# Encoder.net
KiCad netlist of a schematic drawn in Altium Designer
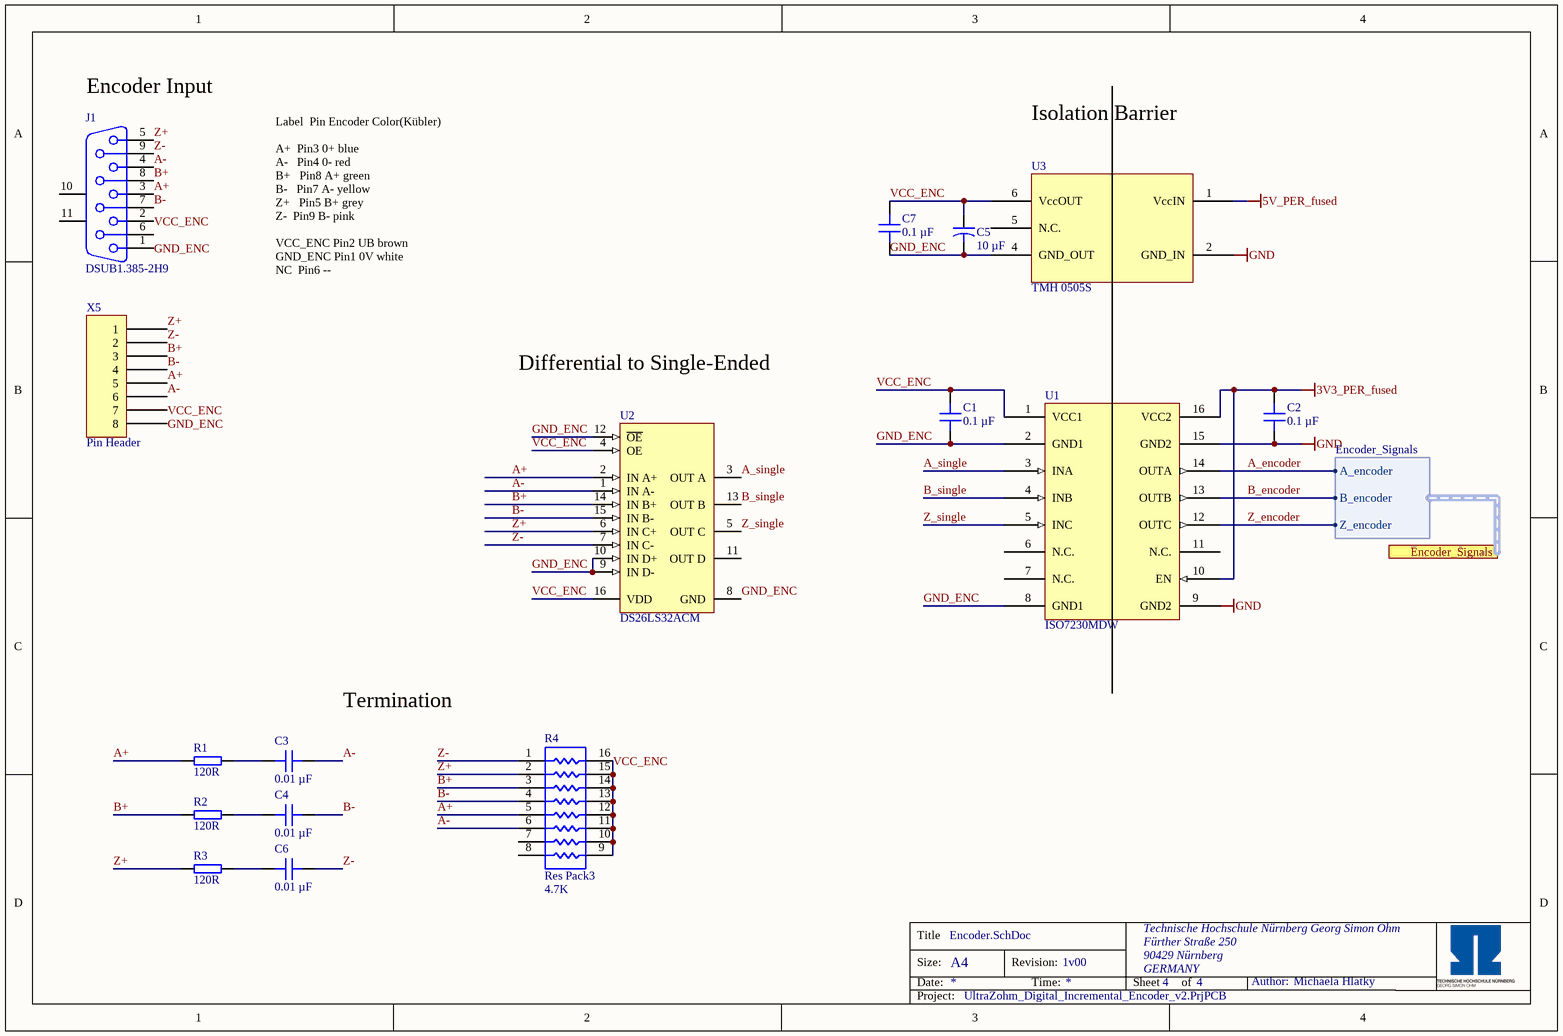
[diagram p0: Encoder.SchDoc]

(export (version "E")
  (design (tool "Eeschema 10.0.6"))
  (components
    (comp (ref "C1")
      (value "0.1 µF")
      (footprint "C_0805")
      (description "Capacitor 0805, 50 VDC, 0.1 µF, X7R")
      (fields
        (field (name "MANUFACTURER PART NUMBER") "C0805C104J5RECTU")
        (field (name "MANUFACTURER") "KEMET")
        (field (name "CREATED FROM") "MGremer")
      )
      (libsource (lib "user") (part "Capacitor"))
    )
    (comp (ref "C2")
      (value "0.1 µF")
      (footprint "C_0805")
      (description "Capacitor 0805, 50 VDC, 0.1 µF, X7R")
      (fields
        (field (name "MANUFACTURER PART NUMBER") "C0805C104J5RECTU")
        (field (name "MANUFACTURER") "KEMET")
        (field (name "CREATED FROM") "MGremer")
      )
      (libsource (lib "user") (part "Capacitor"))
    )
    (comp (ref "C3")
      (value "0.01 µF")
      (footprint "C_0805")
      (description "Capacitor 0805, 100 VDC, 0.01 µF, X7R")
      (fields
        (field (name "MANUFACTURER PART NUMBER") "GRM21BR72A103KA01L")
        (field (name "MANUFACTURER") "Murata Electronics")
        (field (name "CREATED FROM") "MGremer")
      )
      (libsource (lib "user") (part "Capacitor"))
    )
    (comp (ref "C4")
      (value "0.01 µF")
      (footprint "C_0805")
      (description "Capacitor 0805, 100 VDC, 0.01 µF, X7R")
      (fields
        (field (name "MANUFACTURER PART NUMBER") "GRM21BR72A103KA01L")
        (field (name "MANUFACTURER") "Murata Electronics")
        (field (name "CREATED FROM") "MGremer")
      )
      (libsource (lib "user") (part "Capacitor"))
    )
    (comp (ref "C5")
      (value "10 µF")
      (footprint "CAPR5-4X5")
      (description "Capacitor; 2 Leads")
      (fields
        (field (name "MANUFACTURER PART NUMBER") "CAPR5-4X5")
        (field (name "PUBLISHER") "Altium Limited")
        (field (name "CREATED FROM") "MHlatky")
      )
      (libsource (lib "user") (part "Cap2"))
    )
    (comp (ref "C6")
      (value "0.01 µF")
      (footprint "C_0805")
      (description "Capacitor 0805, 100 VDC, 0.01 µF, X7R")
      (fields
        (field (name "MANUFACTURER PART NUMBER") "GRM21BR72A103KA01L")
        (field (name "MANUFACTURER") "Murata Electronics")
        (field (name "CREATED FROM") "MGremer")
      )
      (libsource (lib "user") (part "Capacitor"))
    )
    (comp (ref "C7")
      (value "0.1 µF")
      (footprint "C_0805")
      (description "Capacitor 0805, 50 VDC, 0.1 µF, X7R")
      (fields
        (field (name "MANUFACTURER PART NUMBER") "C0805C104J5RECTU")
        (field (name "MANUFACTURER") "KEMET")
        (field (name "CREATED FROM") "MGremer")
      )
      (libsource (lib "user") (part "Capacitor"))
    )
    (comp (ref "J1")
      (value "DSUB1.385-2H9")
      (footprint "DSUB1.385-2H9")
      (description "Connector; D Subminiature; 9 Position; Right Angle; Pitch 1.385 mm")
      (fields
        (field (name "MANUFACTURER") "Altium")
        (field (name "PUBLISHER") "Altium Limited")
        (field (name "CREATED FROM") "MHlatky")
      )
      (libsource (lib "user") (part "D Connector 9"))
    )
    (comp (ref "R1")
      (value "120R")
      (footprint "RES 0603_1608")
      (description "SMD resistor E24 series")
      (fields
        (field (name "MANUFACTURER PART NUMBER") "RK73B1JTTD121J")
        (field (name "MANUFACTURER") "KOA Speer")
        (field (name "CREATED FROM") "MGremer")
      )
      (libsource (lib "user") (part "Resistor"))
    )
    (comp (ref "R2")
      (value "120R")
      (footprint "RES 0603_1608")
      (description "SMD resistor E24 series")
      (fields
        (field (name "MANUFACTURER PART NUMBER") "RK73B1JTTD121J")
        (field (name "MANUFACTURER") "KOA Speer")
        (field (name "CREATED FROM") "MGremer")
      )
      (libsource (lib "user") (part "Resistor"))
    )
    (comp (ref "R3")
      (value "120R")
      (footprint "RES 0603_1608")
      (description "SMD resistor E24 series")
      (fields
        (field (name "MANUFACTURER PART NUMBER") "RK73B1JTTD121J")
        (field (name "MANUFACTURER") "KOA Speer")
        (field (name "CREATED FROM") "MGremer")
      )
      (libsource (lib "user") (part "Resistor"))
    )
    (comp (ref "R4")
      (value "Res Pack3")
      (footprint "SO-16_N")
      (description "SOIC, 16-Leads, Body 9.9x3.9mm, Pitch 1.27mm, IPC Medium Density")
      (fields
        (field (name "ALTIUM_VALUE") "4.7K")
        (field (name "PUBLISHER") "Altium Limited")
        (field (name "CREATED FROM") "MHlatky")
      )
      (libsource (lib "user") (part "Res Pack3"))
    )
    (comp (ref "U1")
      (value "ISO7230MDW")
      (footprint "TI ISO7230 SOIC")
      (description "ISO723xx High-Speed, Triple-Channel Digital Isolators")
      (fields (field (name "MANUFACTURER") "Analog Devices") (field (name "CREATED FROM") "MHlatky"))
      (libsource (lib "user") (part "TI ISO7230"))
    )
    (comp (ref "U2")
      (value "DS26LS32ACM")
      (footprint "M16A_M")
      (description "DS26LS32AC/DS26LS32C/DS26LS32M/DS26LS33M Quad Differential Line Receivers")
      (fields
        (field (name "MANUFACTURER") "Texas Instruments")
        (field (name "PUBLISHER") "Altium Limited")
        (field (name "CREATED FROM") "MHlatky")
      )
      (libsource (lib "user") (part "DS26LS32ACM"))
    )
    (comp (ref "U3")
      (value "TMH 0505S")
      (footprint "SIL-6(7)")
      (fields (field (name "MANUFACTURER") "Traco") (field (name "CREATED FROM") "MHlatky"))
      (libsource (lib "user") (part "TRACO TMH 0505S"))
    )
    (comp (ref "X5")
      (value "Pin Header")
      (footprint "HDR1X8")
      (description "8 Pin")
      (fields (field (name "MANUFACTURER PART NUMBER") "HDR1X8") (field (name "CREATED FROM") "MHlatky"))
      (libsource (lib "user") (part "8 Pin"))
    )
  )
  (nets
    (net (code "2") (name "/A+") (class "Default")
      (node (ref "J1") (pin "3") (pinfunction "3_3") (pintype "passive"))
      (node (ref "R1") (pin "1") (pinfunction "1_1") (pintype "passive"))
      (node (ref "R4") (pin "5") (pinfunction "5_5") (pintype "passive"))
      (node (ref "U2") (pin "2") (pinfunction "IN_A+_2") (pintype "input"))
      (node (ref "X5") (pin "5") (pinfunction "5_5") (pintype "passive"))
    )
    (net (code "3") (name "/A-") (class "Default")
      (node (ref "C3") (pin "2") (pinfunction "2_2") (pintype "passive"))
      (node (ref "J1") (pin "4") (pinfunction "4_4") (pintype "passive"))
      (node (ref "R4") (pin "6") (pinfunction "6_6") (pintype "passive"))
      (node (ref "U2") (pin "1") (pinfunction "IN_A-_1") (pintype "input"))
      (node (ref "X5") (pin "6") (pinfunction "6_6") (pintype "passive"))
    )
    (net (code "4") (name "/A_encoder") (class "Default")
      (node (ref "U1") (pin "14") (pinfunction "OUTA_14") (pintype "output"))
    )
    (net (code "5") (name "/A_single") (class "Default")
      (node (ref "U1") (pin "3") (pinfunction "INA_3") (pintype "input"))
      (node (ref "U2") (pin "3") (pinfunction "OUT_A_3") (pintype "tri_state"))
    )
    (net (code "6") (name "/B+") (class "Default")
      (node (ref "J1") (pin "8") (pinfunction "8_8") (pintype "passive"))
      (node (ref "R2") (pin "1") (pinfunction "1_1") (pintype "passive"))
      (node (ref "R4") (pin "3") (pinfunction "3_3") (pintype "passive"))
      (node (ref "U2") (pin "14") (pinfunction "IN_B+_14") (pintype "input"))
      (node (ref "X5") (pin "3") (pinfunction "3_3") (pintype "passive"))
    )
    (net (code "7") (name "/B-") (class "Default")
      (node (ref "C4") (pin "2") (pinfunction "2_2") (pintype "passive"))
      (node (ref "J1") (pin "7") (pinfunction "7_7") (pintype "passive"))
      (node (ref "R4") (pin "4") (pinfunction "4_4") (pintype "passive"))
      (node (ref "U2") (pin "15") (pinfunction "IN_B-_15") (pintype "input"))
      (node (ref "X5") (pin "4") (pinfunction "4_4") (pintype "passive"))
    )
    (net (code "8") (name "/B_encoder") (class "Default")
      (node (ref "U1") (pin "13") (pinfunction "OUTB_13") (pintype "output"))
    )
    (net (code "9") (name "/B_single") (class "Default")
      (node (ref "U1") (pin "4") (pinfunction "INB_4") (pintype "input"))
      (node (ref "U2") (pin "13") (pinfunction "OUT_B_13") (pintype "tri_state"))
    )
    (net (code "10") (name "/GND_ENC") (class "Default")
      (node (ref "C1") (pin "1") (pinfunction "1_1") (pintype "passive"))
      (node (ref "C5") (pin "2") (pinfunction "2_2") (pintype "passive"))
      (node (ref "C7") (pin "1") (pinfunction "1_1") (pintype "passive"))
      (node (ref "J1") (pin "1") (pinfunction "1_1") (pintype "passive"))
      (node (ref "U1") (pin "2") (pinfunction "GND1_2") (pintype "passive"))
      (node (ref "U1") (pin "8") (pinfunction "GND1_8") (pintype "passive"))
      (node (ref "U2") (pin "10") (pinfunction "IN_D+_10") (pintype "input"))
      (node (ref "U2") (pin "12") (pinfunction "~{OE}_12") (pintype "input"))
      (node (ref "U2") (pin "8") (pinfunction "GND_8") (pintype "power_in"))
      (node (ref "U2") (pin "9") (pinfunction "IN_D-_9") (pintype "input"))
      (node (ref "U3") (pin "4") (pinfunction "GND_OUT_4") (pintype "passive"))
      (node (ref "X5") (pin "8") (pinfunction "8_8") (pintype "passive"))
    )
    (net (code "11") (name "/VCC_ENC") (class "Default")
      (node (ref "C1") (pin "2") (pinfunction "2_2") (pintype "passive"))
      (node (ref "C5") (pin "1") (pinfunction "1_1") (pintype "passive"))
      (node (ref "C7") (pin "2") (pinfunction "2_2") (pintype "passive"))
      (node (ref "J1") (pin "2") (pinfunction "2_2") (pintype "passive"))
      (node (ref "R4") (pin "10") (pinfunction "10_10") (pintype "passive"))
      (node (ref "R4") (pin "11") (pinfunction "11_11") (pintype "passive"))
      (node (ref "R4") (pin "12") (pinfunction "12_12") (pintype "passive"))
      (node (ref "R4") (pin "13") (pinfunction "13_13") (pintype "passive"))
      (node (ref "R4") (pin "14") (pinfunction "14_14") (pintype "passive"))
      (node (ref "R4") (pin "15") (pinfunction "15_15") (pintype "passive"))
      (node (ref "R4") (pin "16") (pinfunction "16_16") (pintype "passive"))
      (node (ref "R4") (pin "9") (pinfunction "9_9") (pintype "passive"))
      (node (ref "U1") (pin "1") (pinfunction "VCC1_1") (pintype "passive"))
      (node (ref "U2") (pin "16") (pinfunction "VDD_16") (pintype "power_in"))
      (node (ref "U2") (pin "4") (pinfunction "OE_4") (pintype "input"))
      (node (ref "U3") (pin "6") (pinfunction "VccOUT_6") (pintype "passive"))
      (node (ref "X5") (pin "7") (pinfunction "7_7") (pintype "passive"))
    )
    (net (code "12") (name "/Z+") (class "Default")
      (node (ref "J1") (pin "5") (pinfunction "5_5") (pintype "passive"))
      (node (ref "R3") (pin "1") (pinfunction "1_1") (pintype "passive"))
      (node (ref "R4") (pin "2") (pinfunction "2_2") (pintype "passive"))
      (node (ref "U2") (pin "6") (pinfunction "IN_C+_6") (pintype "input"))
      (node (ref "X5") (pin "1") (pinfunction "1_1") (pintype "passive"))
    )
    (net (code "13") (name "/Z-") (class "Default")
      (node (ref "C6") (pin "2") (pinfunction "2_2") (pintype "passive"))
      (node (ref "J1") (pin "9") (pinfunction "9_9") (pintype "passive"))
      (node (ref "R4") (pin "1") (pinfunction "1_1") (pintype "passive"))
      (node (ref "U2") (pin "7") (pinfunction "IN_C-_7") (pintype "input"))
      (node (ref "X5") (pin "2") (pinfunction "2_2") (pintype "passive"))
    )
    (net (code "14") (name "/Z_encoder") (class "Default")
      (node (ref "U1") (pin "12") (pinfunction "OUTC_12") (pintype "output"))
    )
    (net (code "15") (name "/Z_single") (class "Default")
      (node (ref "U1") (pin "5") (pinfunction "INC_5") (pintype "input"))
      (node (ref "U2") (pin "5") (pinfunction "OUT_C_5") (pintype "tri_state"))
    )
    (net (code "17") (name "3V3_PER_fused") (class "Default")
      (node (ref "C2") (pin "2") (pinfunction "2_2") (pintype "passive"))
      (node (ref "U1") (pin "10") (pinfunction "EN_10") (pintype "input"))
      (node (ref "U1") (pin "16") (pinfunction "VCC2_16") (pintype "passive"))
    )
    (net (code "18") (name "5V_PER_fused") (class "Default")
      (node (ref "U3") (pin "1") (pinfunction "VccIN_1") (pintype "passive"))
    )
    (net (code "19") (name "GND") (class "Default")
      (node (ref "C2") (pin "1") (pinfunction "1_1") (pintype "passive"))
      (node (ref "U1") (pin "15") (pinfunction "GND2_15") (pintype "passive"))
      (node (ref "U1") (pin "9") (pinfunction "GND2_9") (pintype "passive"))
      (node (ref "U3") (pin "2") (pinfunction "GND_IN_2") (pintype "passive"))
    )
    (net (code "20") (name "Net-(C3-Pad1)") (class "Default")
      (node (ref "C3") (pin "1") (pinfunction "1_1") (pintype "passive"))
      (node (ref "R1") (pin "2") (pinfunction "2_2") (pintype "passive"))
    )
    (net (code "21") (name "Net-(C4-Pad1)") (class "Default")
      (node (ref "C4") (pin "1") (pinfunction "1_1") (pintype "passive"))
      (node (ref "R2") (pin "2") (pinfunction "2_2") (pintype "passive"))
    )
    (net (code "22") (name "Net-(C6-Pad1)") (class "Default")
      (node (ref "C6") (pin "1") (pinfunction "1_1") (pintype "passive"))
      (node (ref "R3") (pin "2") (pinfunction "2_2") (pintype "passive"))
    )
    (net (code "23") (name "unconnected-(J1-MH1-Pad10)") (class "Default")
      (node (ref "J1") (pin "10") (pinfunction "MH1_10") (pintype "passive"))
    )
    (net (code "24") (name "unconnected-(J1-MH2-Pad11)") (class "Default")
      (node (ref "J1") (pin "11") (pinfunction "MH2_11") (pintype "passive"))
    )
    (net (code "25") (name "unconnected-(J1-Pad6)") (class "Default")
      (node (ref "J1") (pin "6") (pinfunction "6_6") (pintype "passive"))
    )
    (net (code "26") (name "unconnected-(R4-Pad7)") (class "Default")
      (node (ref "R4") (pin "7") (pinfunction "7_7") (pintype "passive"))
    )
    (net (code "27") (name "unconnected-(R4-Pad8)") (class "Default")
      (node (ref "R4") (pin "8") (pinfunction "8_8") (pintype "passive"))
    )
    (net (code "28") (name "unconnected-(U1-N.C.-Pad6)") (class "Default")
      (node (ref "U1") (pin "6") (pinfunction "N.C._6") (pintype "passive"))
    )
    (net (code "29") (name "unconnected-(U1-N.C.-Pad7)") (class "Default")
      (node (ref "U1") (pin "7") (pinfunction "N.C._7") (pintype "passive"))
    )
    (net (code "30") (name "unconnected-(U1-N.C.-Pad11)") (class "Default")
      (node (ref "U1") (pin "11") (pinfunction "N.C._11") (pintype "passive"))
    )
    (net (code "31") (name "unconnected-(U2-OUT_D-Pad11)") (class "Default")
      (node (ref "U2") (pin "11") (pinfunction "OUT_D_11") (pintype "tri_state"))
    )
    (net (code "32") (name "unconnected-(U3-N.C.-Pad5)") (class "Default")
      (node (ref "U3") (pin "5") (pinfunction "N.C._5") (pintype "passive"))
    )
  )
)
